# 08_Misc_3.net
KiCad netlist of a schematic drawn in Altium Designer
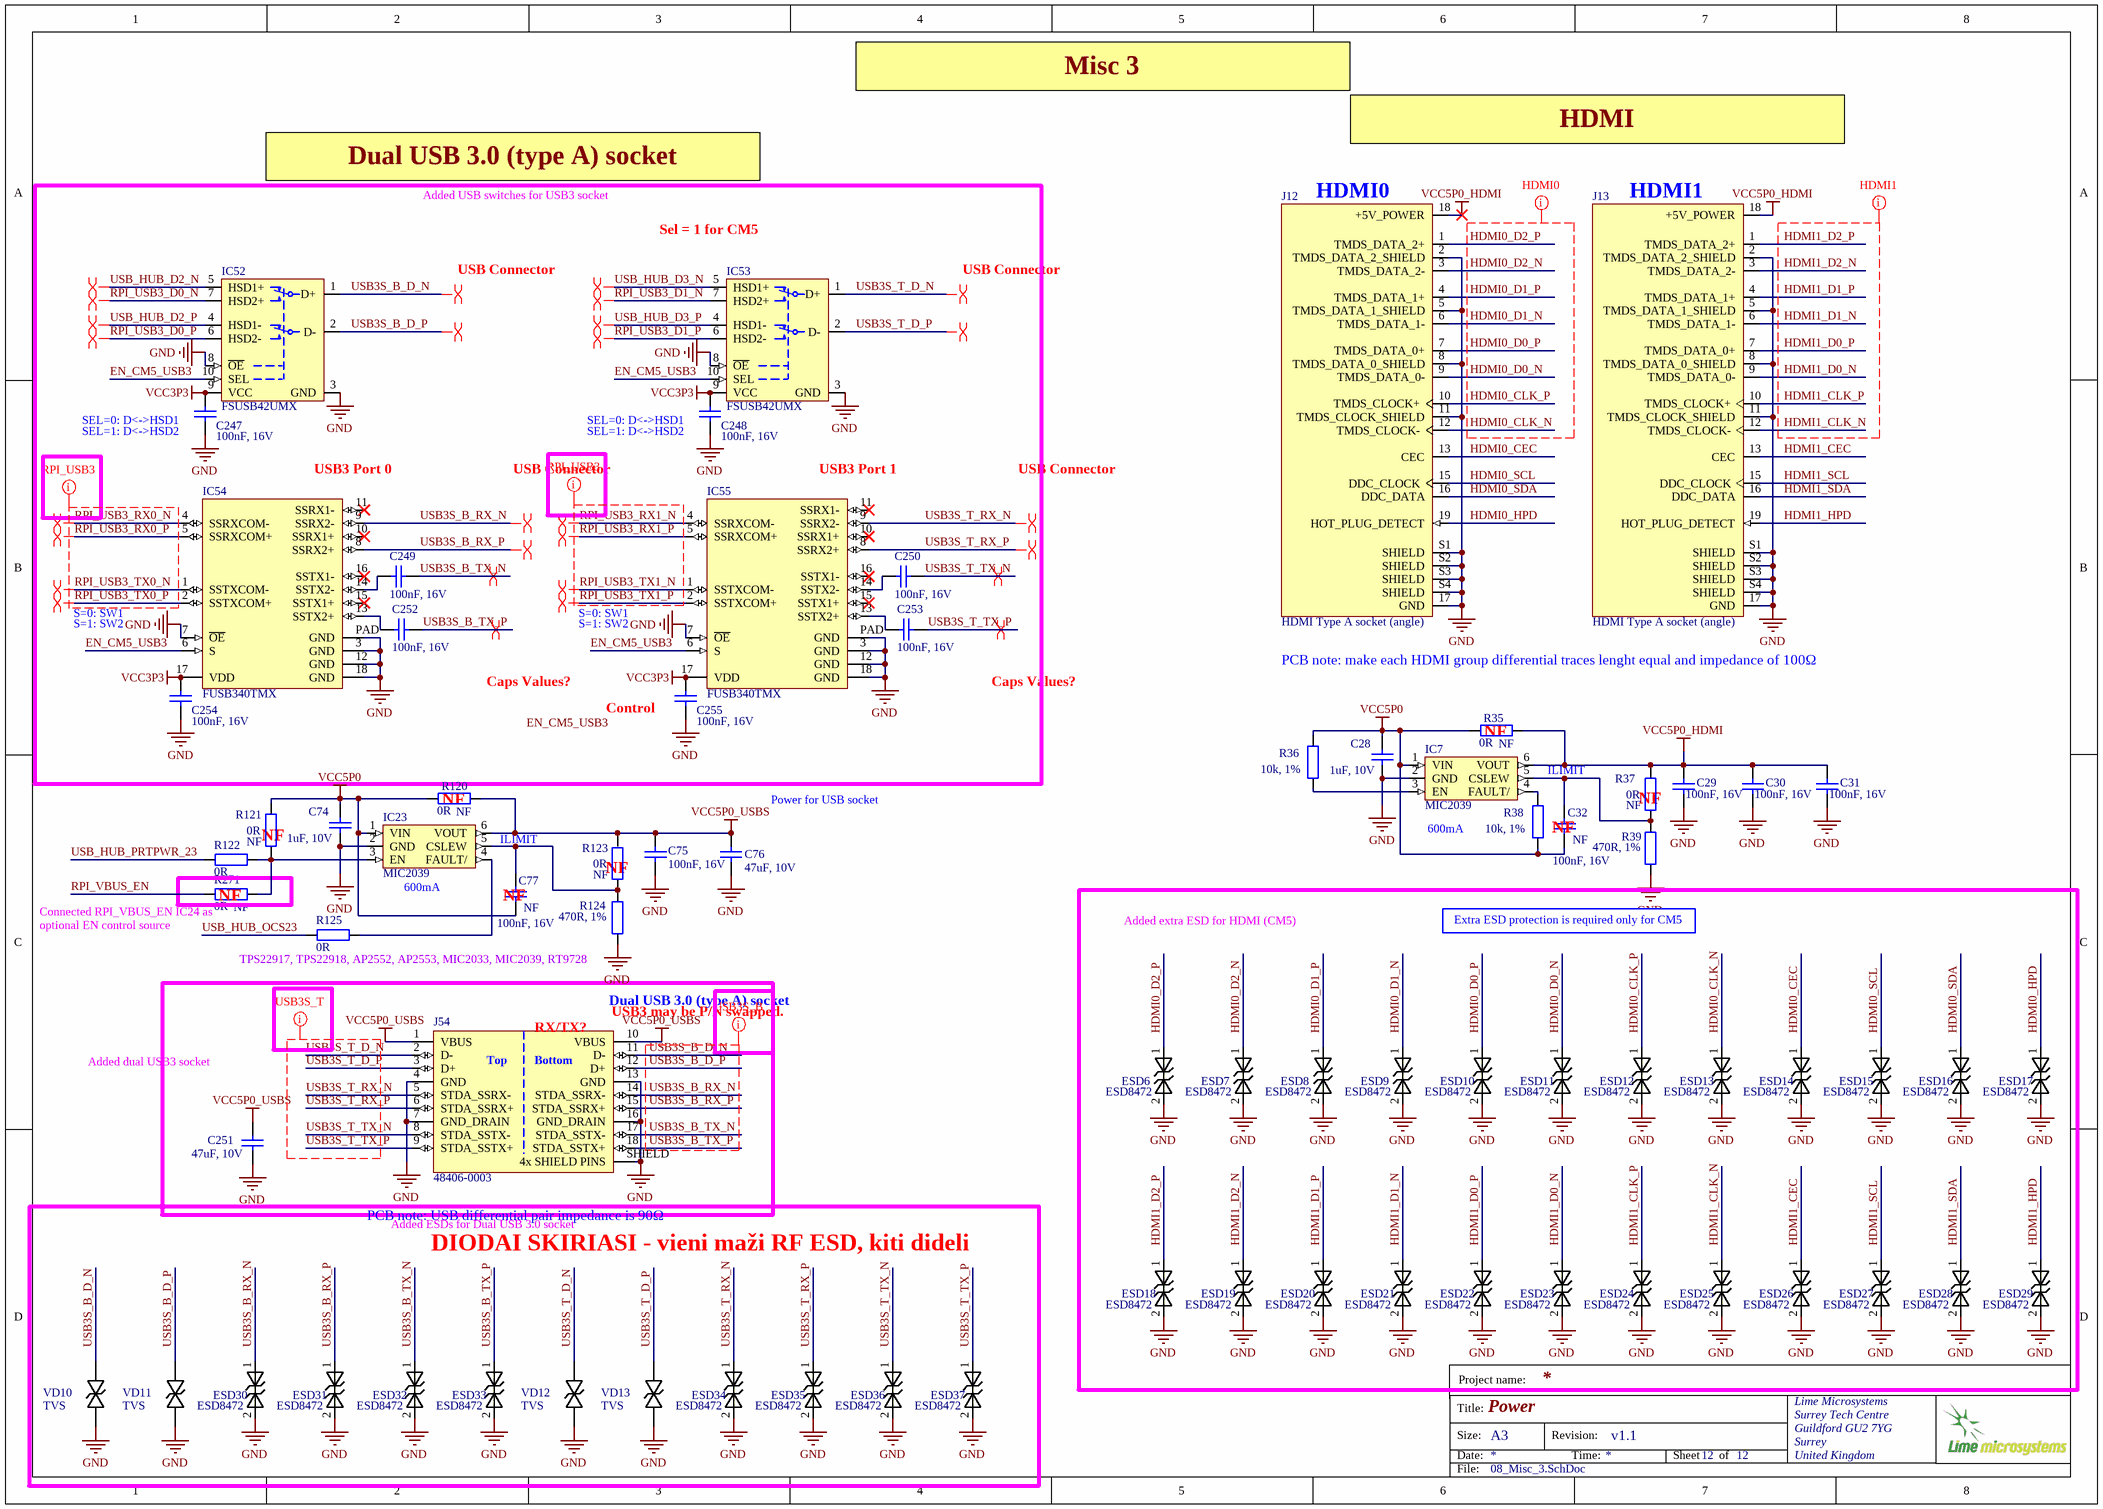
[diagram p0: 08_Misc_3.SchDoc]

(export (version "E")
  (design (tool "Eeschema 10.0.6"))
  (components
    (comp (ref "C28")
      (value "1uF, 10V")
      (footprint "CAP0402")
      (fields (field (name "MANUFACTURER") "Yageo"))
      (libsource (lib "") (part "Cap_0402_1"))
    )
    (comp (ref "C29")
      (value "100nF, 16V")
      (footprint "CAP0402")
      (fields
        (field (name "MANUFACTURER") "Murata Electronics")
        (field (name "TOLERANCE") "10 %")
        (field (name "MANUFACTURER PART NUMBER") "GRM155R71C104KA88D")
      )
      (libsource (lib "") (part "Cap_0402_1"))
    )
    (comp (ref "C30")
      (value "100nF, 16V")
      (footprint "CAP0402")
      (fields
        (field (name "MANUFACTURER") "Murata Electronics")
        (field (name "TOLERANCE") "10 %")
        (field (name "MANUFACTURER PART NUMBER") "GRM155R71C104KA88D")
      )
      (libsource (lib "") (part "Cap_0402_1"))
    )
    (comp (ref "C31")
      (value "100nF, 16V")
      (footprint "CAP0402")
      (fields
        (field (name "MANUFACTURER") "Murata Electronics")
        (field (name "TOLERANCE") "10 %")
        (field (name "MANUFACTURER PART NUMBER") "GRM155R71C104KA88D")
      )
      (libsource (lib "") (part "Cap_0402_1"))
    )
    (comp (ref "C32")
      (value "100nF, 16V")
      (footprint "CAP0402")
      (fields
        (field (name "ASSEMBLY INFO") "NF")
        (field (name "MANUFACTURER") "Murata Electronics")
        (field (name "TOLERANCE") "10 %")
        (field (name "MANUFACTURER PART NUMBER") "GRM155R71C104KA88D")
      )
      (libsource (lib "") (part "Cap_0402_1"))
    )
    (comp (ref "C74")
      (value "1uF, 10V")
      (footprint "CAP0402")
      (fields (field (name "MANUFACTURER") "Yageo"))
      (libsource (lib "") (part "Cap_0402_1"))
    )
    (comp (ref "C75")
      (value "100nF, 16V")
      (footprint "CAP0402")
      (fields
        (field (name "MANUFACTURER") "Murata Electronics")
        (field (name "TOLERANCE") "10 %")
        (field (name "MANUFACTURER PART NUMBER") "GRM155R71C104KA88D")
      )
      (libsource (lib "") (part "Cap_0402_1"))
    )
    (comp (ref "C76")
      (value "47uF, 10V")
      (footprint "CAP1206")
      (fields (field (name "TOLERANCE") "±20%") (field (name "MANUFACTURER") "TDK Corporation"))
      (libsource (lib "LimeFPGAboard_schLib") (part "Cap_1206"))
    )
    (comp (ref "C77")
      (value "100nF, 16V")
      (footprint "CAP0402")
      (fields
        (field (name "ASSEMBLY INFO") "NF")
        (field (name "MANUFACTURER") "Murata Electronics")
        (field (name "TOLERANCE") "10 %")
        (field (name "MANUFACTURER PART NUMBER") "GRM155R71C104KA88D")
      )
      (libsource (lib "") (part "Cap_0402_1"))
    )
    (comp (ref "C247")
      (value "100nF, 16V")
      (footprint "CAP0402")
      (fields
        (field (name "MANUFACTURER") "Murata Electronics")
        (field (name "TOLERANCE") "10 %")
        (field (name "MANUFACTURER PART NUMBER") "GRM155R71C104KA88D")
      )
      (libsource (lib "LimeMicroAltiumLib_schLib") (part "Cap_0402"))
    )
    (comp (ref "C248")
      (value "100nF, 16V")
      (footprint "CAP0402")
      (fields
        (field (name "MANUFACTURER") "Murata Electronics")
        (field (name "TOLERANCE") "10 %")
        (field (name "MANUFACTURER PART NUMBER") "GRM155R71C104KA88D")
      )
      (libsource (lib "LimeMicroAltiumLib_schLib") (part "Cap_0402"))
    )
    (comp (ref "C249")
      (value "100nF, 16V")
      (footprint "CAP0402")
      (fields
        (field (name "MANUFACTURER") "Murata Electronics")
        (field (name "TOLERANCE") "10 %")
        (field (name "MANUFACTURER PART NUMBER") "GRM155R71C104KA88D")
      )
      (libsource (lib "LimeMicroAltiumLib_schLib") (part "Cap_0402"))
    )
    (comp (ref "C250")
      (value "100nF, 16V")
      (footprint "CAP0402")
      (fields
        (field (name "MANUFACTURER") "Murata Electronics")
        (field (name "TOLERANCE") "10 %")
        (field (name "MANUFACTURER PART NUMBER") "GRM155R71C104KA88D")
      )
      (libsource (lib "LimeMicroAltiumLib_schLib") (part "Cap_0402"))
    )
    (comp (ref "C251")
      (value "47uF, 10V")
      (footprint "CAP1206")
      (fields (field (name "TOLERANCE") "±20%") (field (name "MANUFACTURER") "TDK Corporation"))
      (libsource (lib "LimeFPGAboard_schLib") (part "Cap_1206"))
    )
    (comp (ref "C252")
      (value "100nF, 16V")
      (footprint "CAP0402")
      (fields
        (field (name "MANUFACTURER") "Murata Electronics")
        (field (name "TOLERANCE") "10 %")
        (field (name "MANUFACTURER PART NUMBER") "GRM155R71C104KA88D")
      )
      (libsource (lib "LimeMicroAltiumLib_schLib") (part "Cap_0402"))
    )
    (comp (ref "C253")
      (value "100nF, 16V")
      (footprint "CAP0402")
      (fields
        (field (name "MANUFACTURER") "Murata Electronics")
        (field (name "TOLERANCE") "10 %")
        (field (name "MANUFACTURER PART NUMBER") "GRM155R71C104KA88D")
      )
      (libsource (lib "LimeMicroAltiumLib_schLib") (part "Cap_0402"))
    )
    (comp (ref "C254")
      (value "100nF, 16V")
      (footprint "CAP0402")
      (fields
        (field (name "MANUFACTURER") "Murata Electronics")
        (field (name "TOLERANCE") "10 %")
        (field (name "MANUFACTURER PART NUMBER") "GRM155R71C104KA88D")
      )
      (libsource (lib "LimeMicroAltiumLib_schLib") (part "Cap_0402"))
    )
    (comp (ref "C255")
      (value "100nF, 16V")
      (footprint "CAP0402")
      (fields
        (field (name "MANUFACTURER") "Murata Electronics")
        (field (name "TOLERANCE") "10 %")
        (field (name "MANUFACTURER PART NUMBER") "GRM155R71C104KA88D")
      )
      (libsource (lib "LimeMicroAltiumLib_schLib") (part "Cap_0402"))
    )
    (comp (ref "ESD6")
      (value "ESD8472")
      (footprint "ESD8472_X3DFN2")
      (fields (field (name "MANUFACTURER") "ON Semiconductor"))
      (libsource (lib "LimeMicroAltiumLib_schLib") (part "ESD8472"))
    )
    (comp (ref "ESD7")
      (value "ESD8472")
      (footprint "ESD8472_X3DFN2")
      (fields (field (name "MANUFACTURER") "ON Semiconductor"))
      (libsource (lib "LimeMicroAltiumLib_schLib") (part "ESD8472"))
    )
    (comp (ref "ESD8")
      (value "ESD8472")
      (footprint "ESD8472_X3DFN2")
      (fields (field (name "MANUFACTURER") "ON Semiconductor"))
      (libsource (lib "LimeMicroAltiumLib_schLib") (part "ESD8472"))
    )
    (comp (ref "ESD9")
      (value "ESD8472")
      (footprint "ESD8472_X3DFN2")
      (fields (field (name "MANUFACTURER") "ON Semiconductor"))
      (libsource (lib "LimeMicroAltiumLib_schLib") (part "ESD8472"))
    )
    (comp (ref "ESD10")
      (value "ESD8472")
      (footprint "ESD8472_X3DFN2")
      (fields (field (name "MANUFACTURER") "ON Semiconductor"))
      (libsource (lib "LimeMicroAltiumLib_schLib") (part "ESD8472"))
    )
    (comp (ref "ESD11")
      (value "ESD8472")
      (footprint "ESD8472_X3DFN2")
      (fields (field (name "MANUFACTURER") "ON Semiconductor"))
      (libsource (lib "LimeMicroAltiumLib_schLib") (part "ESD8472"))
    )
    (comp (ref "ESD12")
      (value "ESD8472")
      (footprint "ESD8472_X3DFN2")
      (fields (field (name "MANUFACTURER") "ON Semiconductor"))
      (libsource (lib "LimeMicroAltiumLib_schLib") (part "ESD8472"))
    )
    (comp (ref "ESD13")
      (value "ESD8472")
      (footprint "ESD8472_X3DFN2")
      (fields (field (name "MANUFACTURER") "ON Semiconductor"))
      (libsource (lib "LimeMicroAltiumLib_schLib") (part "ESD8472"))
    )
    (comp (ref "ESD14")
      (value "ESD8472")
      (footprint "ESD8472_X3DFN2")
      (fields (field (name "MANUFACTURER") "ON Semiconductor"))
      (libsource (lib "LimeMicroAltiumLib_schLib") (part "ESD8472"))
    )
    (comp (ref "ESD15")
      (value "ESD8472")
      (footprint "ESD8472_X3DFN2")
      (fields (field (name "MANUFACTURER") "ON Semiconductor"))
      (libsource (lib "LimeMicroAltiumLib_schLib") (part "ESD8472"))
    )
    (comp (ref "ESD16")
      (value "ESD8472")
      (footprint "ESD8472_X3DFN2")
      (fields (field (name "MANUFACTURER") "ON Semiconductor"))
      (libsource (lib "LimeMicroAltiumLib_schLib") (part "ESD8472"))
    )
    (comp (ref "ESD17")
      (value "ESD8472")
      (footprint "ESD8472_X3DFN2")
      (fields (field (name "MANUFACTURER") "ON Semiconductor"))
      (libsource (lib "LimeMicroAltiumLib_schLib") (part "ESD8472"))
    )
    (comp (ref "ESD18")
      (value "ESD8472")
      (footprint "ESD8472_X3DFN2")
      (fields (field (name "MANUFACTURER") "ON Semiconductor"))
      (libsource (lib "LimeMicroAltiumLib_schLib") (part "ESD8472"))
    )
    (comp (ref "ESD19")
      (value "ESD8472")
      (footprint "ESD8472_X3DFN2")
      (fields (field (name "MANUFACTURER") "ON Semiconductor"))
      (libsource (lib "LimeMicroAltiumLib_schLib") (part "ESD8472"))
    )
    (comp (ref "ESD20")
      (value "ESD8472")
      (footprint "ESD8472_X3DFN2")
      (fields (field (name "MANUFACTURER") "ON Semiconductor"))
      (libsource (lib "LimeMicroAltiumLib_schLib") (part "ESD8472"))
    )
    (comp (ref "ESD21")
      (value "ESD8472")
      (footprint "ESD8472_X3DFN2")
      (fields (field (name "MANUFACTURER") "ON Semiconductor"))
      (libsource (lib "LimeMicroAltiumLib_schLib") (part "ESD8472"))
    )
    (comp (ref "ESD22")
      (value "ESD8472")
      (footprint "ESD8472_X3DFN2")
      (fields (field (name "MANUFACTURER") "ON Semiconductor"))
      (libsource (lib "LimeMicroAltiumLib_schLib") (part "ESD8472"))
    )
    (comp (ref "ESD23")
      (value "ESD8472")
      (footprint "ESD8472_X3DFN2")
      (fields (field (name "MANUFACTURER") "ON Semiconductor"))
      (libsource (lib "LimeMicroAltiumLib_schLib") (part "ESD8472"))
    )
    (comp (ref "ESD24")
      (value "ESD8472")
      (footprint "ESD8472_X3DFN2")
      (fields (field (name "MANUFACTURER") "ON Semiconductor"))
      (libsource (lib "LimeMicroAltiumLib_schLib") (part "ESD8472"))
    )
    (comp (ref "ESD25")
      (value "ESD8472")
      (footprint "ESD8472_X3DFN2")
      (fields (field (name "MANUFACTURER") "ON Semiconductor"))
      (libsource (lib "LimeMicroAltiumLib_schLib") (part "ESD8472"))
    )
    (comp (ref "ESD26")
      (value "ESD8472")
      (footprint "ESD8472_X3DFN2")
      (fields (field (name "MANUFACTURER") "ON Semiconductor"))
      (libsource (lib "LimeMicroAltiumLib_schLib") (part "ESD8472"))
    )
    (comp (ref "ESD27")
      (value "ESD8472")
      (footprint "ESD8472_X3DFN2")
      (fields (field (name "MANUFACTURER") "ON Semiconductor"))
      (libsource (lib "LimeMicroAltiumLib_schLib") (part "ESD8472"))
    )
    (comp (ref "ESD28")
      (value "ESD8472")
      (footprint "ESD8472_X3DFN2")
      (fields (field (name "MANUFACTURER") "ON Semiconductor"))
      (libsource (lib "LimeMicroAltiumLib_schLib") (part "ESD8472"))
    )
    (comp (ref "ESD29")
      (value "ESD8472")
      (footprint "ESD8472_X3DFN2")
      (fields (field (name "MANUFACTURER") "ON Semiconductor"))
      (libsource (lib "LimeMicroAltiumLib_schLib") (part "ESD8472"))
    )
    (comp (ref "ESD30")
      (value "ESD8472")
      (footprint "ESD8472_X3DFN2")
      (fields (field (name "MANUFACTURER") "ON Semiconductor"))
      (libsource (lib "LimeMicroAltiumLib_schLib") (part "ESD8472"))
    )
    (comp (ref "ESD31")
      (value "ESD8472")
      (footprint "ESD8472_X3DFN2")
      (fields (field (name "MANUFACTURER") "ON Semiconductor"))
      (libsource (lib "LimeMicroAltiumLib_schLib") (part "ESD8472"))
    )
    (comp (ref "ESD32")
      (value "ESD8472")
      (footprint "ESD8472_X3DFN2")
      (fields (field (name "MANUFACTURER") "ON Semiconductor"))
      (libsource (lib "LimeMicroAltiumLib_schLib") (part "ESD8472"))
    )
    (comp (ref "ESD33")
      (value "ESD8472")
      (footprint "ESD8472_X3DFN2")
      (fields (field (name "MANUFACTURER") "ON Semiconductor"))
      (libsource (lib "LimeMicroAltiumLib_schLib") (part "ESD8472"))
    )
    (comp (ref "ESD34")
      (value "ESD8472")
      (footprint "ESD8472_X3DFN2")
      (fields (field (name "MANUFACTURER") "ON Semiconductor"))
      (libsource (lib "LimeMicroAltiumLib_schLib") (part "ESD8472"))
    )
    (comp (ref "ESD35")
      (value "ESD8472")
      (footprint "ESD8472_X3DFN2")
      (fields (field (name "MANUFACTURER") "ON Semiconductor"))
      (libsource (lib "LimeMicroAltiumLib_schLib") (part "ESD8472"))
    )
    (comp (ref "ESD36")
      (value "ESD8472")
      (footprint "ESD8472_X3DFN2")
      (fields (field (name "MANUFACTURER") "ON Semiconductor"))
      (libsource (lib "LimeMicroAltiumLib_schLib") (part "ESD8472"))
    )
    (comp (ref "ESD37")
      (value "ESD8472")
      (footprint "ESD8472_X3DFN2")
      (fields (field (name "MANUFACTURER") "ON Semiconductor"))
      (libsource (lib "LimeMicroAltiumLib_schLib") (part "ESD8472"))
    )
    (comp (ref "IC7")
      (value "MIC2039")
      (footprint "SOT23-6")
      (fields (field (name "MANUFACTURER") "Microchip"))
      (libsource (lib "LimeMicroAltiumLib_schLib_r04") (part "MIC2033_power_switch"))
    )
    (comp (ref "IC23")
      (value "MIC2039")
      (footprint "SOT23-6")
      (fields (field (name "MANUFACTURER") "Microchip"))
      (libsource (lib "LimeMicroAltiumLib_schLib_r04") (part "MIC2033_power_switch"))
    )
    (comp (ref "IC52")
      (value "FSUSB42UMX")
      (footprint "FSUSB42UMX")
      (fields (field (name "MANUFACTURER") "ON Semiconductor") (field (name "BASE PART NUMBER") "FSUSB42"))
      (libsource (lib "LimeMicroAltiumLib_schLib_r01") (part "FSUSB42UMX"))
    )
    (comp (ref "IC53")
      (value "FSUSB42UMX")
      (footprint "FSUSB42UMX")
      (fields (field (name "MANUFACTURER") "ON Semiconductor") (field (name "BASE PART NUMBER") "FSUSB42"))
      (libsource (lib "LimeMicroAltiumLib_schLib_r01") (part "FSUSB42UMX"))
    )
    (comp (ref "IC54")
      (value "FUSB340TMX")
      (footprint "FUSB340TMX_USB_switch_18-XFQFN")
      (fields (field (name "MANUFACTURER") "ON Semiconductor / Fairchild"))
      (libsource (lib "LimeMicroAltiumLib") (part "FUSB340TMX_USB_switch"))
    )
    (comp (ref "IC55")
      (value "FUSB340TMX")
      (footprint "FUSB340TMX_USB_switch_18-XFQFN")
      (fields (field (name "MANUFACTURER") "ON Semiconductor / Fairchild"))
      (libsource (lib "LimeMicroAltiumLib") (part "FUSB340TMX_USB_switch"))
    )
    (comp (ref "J12")
      (value "HDMI Type A socket (angle)")
      (footprint "HDMI_HD01-19-RA-TH")
      (fields (field (name "MANUFACTURER") "CUI Devices"))
      (libsource (lib "LimeMicroAltiumLib_schLib_r04") (part "HDMI_HD01-19-RA-TH"))
    )
    (comp (ref "J13")
      (value "HDMI Type A socket (angle)")
      (footprint "HDMI_HD01-19-RA-TH")
      (fields (field (name "MANUFACTURER") "CUI Devices"))
      (libsource (lib "LimeMicroAltiumLib_schLib_r04") (part "HDMI_HD01-19-RA-TH"))
    )
    (comp (ref "J54")
      (value "48406-0003")
      (footprint "Dual_USB_48406-0003_Molex")
      (fields (field (name "MANUFACTURER") "Molex"))
      (libsource (lib "LimeMicroAltiumLib") (part "Dual_USB_48406-0003_Molex"))
    )
    (comp (ref "R35")
      (value "0R")
      (footprint "RES0402")
      (fields
        (field (name "ASSEMBLY INFO") "NF")
        (field (name "MANUFACTURER") "Yageo")
        (field (name "TOLERANCE") "Jumper")
      )
      (libsource (lib "") (part "Res_0402_1"))
    )
    (comp (ref "R36")
      (value "10k, 1%")
      (footprint "RES0402")
      (fields (field (name "MANUFACTURER") "Yageo") (field (name "TOLERANCE") "±1%"))
      (libsource (lib "LimeMicroAltiumLib_schLib") (part "Res_0402"))
    )
    (comp (ref "R37")
      (value "0R")
      (footprint "RES0402")
      (fields
        (field (name "ASSEMBLY INFO") "NF")
        (field (name "MANUFACTURER") "Yageo")
        (field (name "TOLERANCE") "Jumper")
      )
      (libsource (lib "") (part "Res_0402_1"))
    )
    (comp (ref "R38")
      (value "10k, 1%")
      (footprint "RES0402")
      (fields (field (name "MANUFACTURER") "Yageo") (field (name "TOLERANCE") "±1%"))
      (libsource (lib "LimeMicroAltiumLib_schLib") (part "Res_0402"))
    )
    (comp (ref "R39")
      (value "470R, 1%")
      (footprint "RES0402")
      (fields (field (name "TOLERANCE") "1%") (field (name "MANUFACTURER") "Yageo"))
      (libsource (lib "") (part "Res_0402_1"))
    )
    (comp (ref "R120")
      (value "0R")
      (footprint "RES0402")
      (fields
        (field (name "ASSEMBLY INFO") "NF")
        (field (name "MANUFACTURER") "Yageo")
        (field (name "TOLERANCE") "Jumper")
      )
      (libsource (lib "") (part "Res_0402_1"))
    )
    (comp (ref "R121")
      (value "0R")
      (footprint "RES0402")
      (fields
        (field (name "ASSEMBLY INFO") "NF")
        (field (name "MANUFACTURER") "Yageo")
        (field (name "TOLERANCE") "Jumper")
      )
      (libsource (lib "") (part "Res_0402_1"))
    )
    (comp (ref "R122")
      (value "0R")
      (footprint "RES0402")
      (fields (field (name "MANUFACTURER") "Yageo") (field (name "TOLERANCE") "Jumper"))
      (libsource (lib "") (part "Res_0402_1"))
    )
    (comp (ref "R123")
      (value "0R")
      (footprint "RES0402")
      (fields
        (field (name "ASSEMBLY INFO") "NF")
        (field (name "MANUFACTURER") "Yageo")
        (field (name "TOLERANCE") "Jumper")
      )
      (libsource (lib "") (part "Res_0402_1"))
    )
    (comp (ref "R124")
      (value "470R, 1%")
      (footprint "RES0402")
      (fields (field (name "TOLERANCE") "1%") (field (name "MANUFACTURER") "Yageo"))
      (libsource (lib "") (part "Res_0402_1"))
    )
    (comp (ref "R125")
      (value "0R")
      (footprint "RES0402")
      (fields (field (name "MANUFACTURER") "Yageo") (field (name "TOLERANCE") "Jumper"))
      (libsource (lib "") (part "Res_0402_1"))
    )
    (comp (ref "R271")
      (value "0R")
      (footprint "RES0402")
      (fields
        (field (name "ASSEMBLY INFO") "NF")
        (field (name "MANUFACTURER") "Yageo")
        (field (name "TOLERANCE") "Jumper")
      )
      (libsource (lib "") (part "Res_0402_1"))
    )
    (comp (ref "VD10")
      (value "TVS")
      (footprint "SOD323")
      (fields
        (field (name "MANUFACTURER PART NUMBER") "SD03LCC")
        (field (name "MANUFACTURER") "Sangdest Microelectronics")
      )
      (libsource (lib "LimeNet-Micro_2v1-SDR") (part "DIODE_TVS"))
    )
    (comp (ref "VD11")
      (value "TVS")
      (footprint "SOD323")
      (fields
        (field (name "MANUFACTURER PART NUMBER") "SD03LCC")
        (field (name "MANUFACTURER") "Sangdest Microelectronics")
      )
      (libsource (lib "LimeNet-Micro_2v1-SDR") (part "DIODE_TVS"))
    )
    (comp (ref "VD12")
      (value "TVS")
      (footprint "SOD323")
      (fields
        (field (name "MANUFACTURER PART NUMBER") "SD03LCC")
        (field (name "MANUFACTURER") "Sangdest Microelectronics")
      )
      (libsource (lib "LimeNet-Micro_2v1-SDR") (part "DIODE_TVS"))
    )
    (comp (ref "VD13")
      (value "TVS")
      (footprint "SOD323")
      (fields
        (field (name "MANUFACTURER PART NUMBER") "SD03LCC")
        (field (name "MANUFACTURER") "Sangdest Microelectronics")
      )
      (libsource (lib "LimeNet-Micro_2v1-SDR") (part "DIODE_TVS"))
    )
  )
  (nets
    (net (code "1") (name "/EN_CM5_USB3") (class "Default")
      (node (ref "IC52") (pin "10") (pinfunction "SEL_10") (pintype "input"))
      (node (ref "IC53") (pin "10") (pinfunction "SEL_10") (pintype "input"))
      (node (ref "IC54") (pin "6") (pinfunction "S_6") (pintype "input"))
      (node (ref "IC55") (pin "6") (pinfunction "S_6") (pintype "input"))
    )
    (net (code "2") (name "/HDMI0_CEC") (class "Default")
      (node (ref "ESD14") (pin "1") (pinfunction "1_1") (pintype "passive"))
      (node (ref "J12") (pin "13") (pinfunction "CEC_13") (pintype "bidirectional"))
    )
    (net (code "3") (name "/HDMI0_CLK_N") (class "Default")
      (node (ref "ESD13") (pin "1") (pinfunction "1_1") (pintype "passive"))
      (node (ref "J12") (pin "12") (pinfunction "TMDS_CLOCK-_12") (pintype "bidirectional"))
    )
    (net (code "4") (name "/HDMI0_CLK_P") (class "Default")
      (node (ref "ESD12") (pin "1") (pinfunction "1_1") (pintype "passive"))
      (node (ref "J12") (pin "10") (pinfunction "TMDS_CLOCK+_10") (pintype "bidirectional"))
    )
    (net (code "5") (name "/HDMI0_D0_N") (class "Default")
      (node (ref "ESD11") (pin "1") (pinfunction "1_1") (pintype "passive"))
      (node (ref "J12") (pin "9") (pinfunction "TMDS_DATA_0-_9") (pintype "bidirectional"))
    )
    (net (code "6") (name "/HDMI0_D0_P") (class "Default")
      (node (ref "ESD10") (pin "1") (pinfunction "1_1") (pintype "passive"))
      (node (ref "J12") (pin "7") (pinfunction "TMDS_DATA_0+_7") (pintype "bidirectional"))
    )
    (net (code "7") (name "/HDMI0_D1_N") (class "Default")
      (node (ref "ESD9") (pin "1") (pinfunction "1_1") (pintype "passive"))
      (node (ref "J12") (pin "6") (pinfunction "TMDS_DATA_1-_6") (pintype "bidirectional"))
    )
    (net (code "8") (name "/HDMI0_D1_P") (class "Default")
      (node (ref "ESD8") (pin "1") (pinfunction "1_1") (pintype "passive"))
      (node (ref "J12") (pin "4") (pinfunction "TMDS_DATA_1+_4") (pintype "bidirectional"))
    )
    (net (code "9") (name "/HDMI0_D2_N") (class "Default")
      (node (ref "ESD7") (pin "1") (pinfunction "1_1") (pintype "passive"))
      (node (ref "J12") (pin "3") (pinfunction "TMDS_DATA_2-_3") (pintype "bidirectional"))
    )
    (net (code "10") (name "/HDMI0_D2_P") (class "Default")
      (node (ref "ESD6") (pin "1") (pinfunction "1_1") (pintype "passive"))
      (node (ref "J12") (pin "1") (pinfunction "TMDS_DATA_2+_1") (pintype "bidirectional"))
    )
    (net (code "11") (name "/HDMI0_HPD") (class "Default")
      (node (ref "ESD17") (pin "1") (pinfunction "1_1") (pintype "passive"))
      (node (ref "J12") (pin "19") (pinfunction "HOT_PLUG_DETECT_19") (pintype "input"))
    )
    (net (code "12") (name "/HDMI0_SCL") (class "Default")
      (node (ref "ESD15") (pin "1") (pinfunction "1_1") (pintype "passive"))
      (node (ref "J12") (pin "15") (pinfunction "DDC_CLOCK_15") (pintype "bidirectional"))
    )
    (net (code "13") (name "/HDMI0_SDA") (class "Default")
      (node (ref "ESD16") (pin "1") (pinfunction "1_1") (pintype "passive"))
      (node (ref "J12") (pin "16") (pinfunction "DDC_DATA_16") (pintype "bidirectional"))
    )
    (net (code "14") (name "/HDMI1_CEC") (class "Default")
      (node (ref "ESD26") (pin "1") (pinfunction "1_1") (pintype "passive"))
      (node (ref "J13") (pin "13") (pinfunction "CEC_13") (pintype "bidirectional"))
    )
    (net (code "15") (name "/HDMI1_CLK_N") (class "Default")
      (node (ref "ESD25") (pin "1") (pinfunction "1_1") (pintype "passive"))
      (node (ref "J13") (pin "12") (pinfunction "TMDS_CLOCK-_12") (pintype "bidirectional"))
    )
    (net (code "16") (name "/HDMI1_CLK_P") (class "Default")
      (node (ref "ESD24") (pin "1") (pinfunction "1_1") (pintype "passive"))
      (node (ref "J13") (pin "10") (pinfunction "TMDS_CLOCK+_10") (pintype "bidirectional"))
    )
    (net (code "17") (name "/HDMI1_D0_N") (class "Default")
      (node (ref "ESD23") (pin "1") (pinfunction "1_1") (pintype "passive"))
      (node (ref "J13") (pin "9") (pinfunction "TMDS_DATA_0-_9") (pintype "bidirectional"))
    )
    (net (code "18") (name "/HDMI1_D0_P") (class "Default")
      (node (ref "ESD22") (pin "1") (pinfunction "1_1") (pintype "passive"))
      (node (ref "J13") (pin "7") (pinfunction "TMDS_DATA_0+_7") (pintype "bidirectional"))
    )
    (net (code "19") (name "/HDMI1_D1_N") (class "Default")
      (node (ref "ESD21") (pin "1") (pinfunction "1_1") (pintype "passive"))
      (node (ref "J13") (pin "6") (pinfunction "TMDS_DATA_1-_6") (pintype "bidirectional"))
    )
    (net (code "20") (name "/HDMI1_D1_P") (class "Default")
      (node (ref "ESD20") (pin "1") (pinfunction "1_1") (pintype "passive"))
      (node (ref "J13") (pin "4") (pinfunction "TMDS_DATA_1+_4") (pintype "bidirectional"))
    )
    (net (code "21") (name "/HDMI1_D2_N") (class "Default")
      (node (ref "ESD19") (pin "1") (pinfunction "1_1") (pintype "passive"))
      (node (ref "J13") (pin "3") (pinfunction "TMDS_DATA_2-_3") (pintype "bidirectional"))
    )
    (net (code "22") (name "/HDMI1_D2_P") (class "Default")
      (node (ref "ESD18") (pin "1") (pinfunction "1_1") (pintype "passive"))
      (node (ref "J13") (pin "1") (pinfunction "TMDS_DATA_2+_1") (pintype "bidirectional"))
    )
    (net (code "23") (name "/HDMI1_HPD") (class "Default")
      (node (ref "ESD29") (pin "1") (pinfunction "1_1") (pintype "passive"))
      (node (ref "J13") (pin "19") (pinfunction "HOT_PLUG_DETECT_19") (pintype "input"))
    )
    (net (code "24") (name "/HDMI1_SCL") (class "Default")
      (node (ref "ESD27") (pin "1") (pinfunction "1_1") (pintype "passive"))
      (node (ref "J13") (pin "15") (pinfunction "DDC_CLOCK_15") (pintype "bidirectional"))
    )
    (net (code "25") (name "/HDMI1_SDA") (class "Default")
      (node (ref "ESD28") (pin "1") (pinfunction "1_1") (pintype "passive"))
      (node (ref "J13") (pin "16") (pinfunction "DDC_DATA_16") (pintype "bidirectional"))
    )
    (net (code "26") (name "/RPI_USB3_D0_N") (class "Default")
      (node (ref "IC52") (pin "7") (pinfunction "HSD2+_7") (pintype "passive"))
    )
    (net (code "27") (name "/RPI_USB3_D0_P") (class "Default")
      (node (ref "IC52") (pin "6") (pinfunction "HSD2-_6") (pintype "passive"))
    )
    (net (code "28") (name "/RPI_USB3_D1_N") (class "Default")
      (node (ref "IC53") (pin "7") (pinfunction "HSD2+_7") (pintype "passive"))
    )
    (net (code "29") (name "/RPI_USB3_D1_P") (class "Default")
      (node (ref "IC53") (pin "6") (pinfunction "HSD2-_6") (pintype "passive"))
    )
    (net (code "30") (name "/RPI_USB3_RX0_N") (class "Default")
      (node (ref "IC54") (pin "4") (pinfunction "SSRXCOM-_4") (pintype "bidirectional"))
    )
    (net (code "31") (name "/RPI_USB3_RX0_P") (class "Default")
      (node (ref "IC54") (pin "5") (pinfunction "SSRXCOM+_5") (pintype "bidirectional"))
    )
    (net (code "32") (name "/RPI_USB3_RX1_N") (class "Default")
      (node (ref "IC55") (pin "4") (pinfunction "SSRXCOM-_4") (pintype "bidirectional"))
    )
    (net (code "33") (name "/RPI_USB3_RX1_P") (class "Default")
      (node (ref "IC55") (pin "5") (pinfunction "SSRXCOM+_5") (pintype "bidirectional"))
    )
    (net (code "34") (name "/RPI_USB3_TX0_N") (class "Default")
      (node (ref "IC54") (pin "1") (pinfunction "SSTXCOM-_1") (pintype "bidirectional"))
    )
    (net (code "35") (name "/RPI_USB3_TX0_P") (class "Default")
      (node (ref "IC54") (pin "2") (pinfunction "SSTXCOM+_2") (pintype "bidirectional"))
    )
    (net (code "36") (name "/RPI_USB3_TX1_N") (class "Default")
      (node (ref "IC55") (pin "1") (pinfunction "SSTXCOM-_1") (pintype "bidirectional"))
    )
    (net (code "37") (name "/RPI_USB3_TX1_P") (class "Default")
      (node (ref "IC55") (pin "2") (pinfunction "SSTXCOM+_2") (pintype "bidirectional"))
    )
    (net (code "38") (name "/RPI_VBUS_EN") (class "Default")
      (node (ref "R271") (pin "2") (pinfunction "2_2") (pintype "passive"))
    )
    (net (code "39") (name "/USB3S_B_D_N") (class "Default")
      (node (ref "IC52") (pin "1") (pinfunction "D+_1") (pintype "passive"))
      (node (ref "J54") (pin "11") (pinfunction "D-_11") (pintype "bidirectional"))
      (node (ref "VD10") (pin "A") (pinfunction "A_A") (pintype "passive"))
    )
    (net (code "40") (name "/USB3S_B_D_P") (class "Default")
      (node (ref "IC52") (pin "2") (pinfunction "D-_2") (pintype "passive"))
      (node (ref "J54") (pin "12") (pinfunction "D+_12") (pintype "bidirectional"))
      (node (ref "VD11") (pin "A") (pinfunction "A_A") (pintype "passive"))
    )
    (net (code "41") (name "/USB3S_B_RX_N") (class "Default")
      (node (ref "ESD30") (pin "1") (pinfunction "1_1") (pintype "passive"))
      (node (ref "IC54") (pin "9") (pinfunction "SSRX2-_9") (pintype "bidirectional"))
      (node (ref "J54") (pin "14") (pinfunction "STDA_SSRX-_14") (pintype "bidirectional"))
    )
    (net (code "42") (name "/USB3S_B_RX_P") (class "Default")
      (node (ref "ESD31") (pin "1") (pinfunction "1_1") (pintype "passive"))
      (node (ref "IC54") (pin "8") (pinfunction "SSRX2+_8") (pintype "bidirectional"))
      (node (ref "J54") (pin "15") (pinfunction "STDA_SSRX+_15") (pintype "bidirectional"))
    )
    (net (code "43") (name "/USB3S_B_TX_N") (class "Default")
      (node (ref "C249") (pin "2") (pinfunction "2_2") (pintype "passive"))
      (node (ref "ESD32") (pin "1") (pinfunction "1_1") (pintype "passive"))
      (node (ref "J54") (pin "17") (pinfunction "STDA_SSTX-_17") (pintype "bidirectional"))
    )
    (net (code "44") (name "/USB3S_B_TX_P") (class "Default")
      (node (ref "C252") (pin "2") (pinfunction "2_2") (pintype "passive"))
      (node (ref "ESD33") (pin "1") (pinfunction "1_1") (pintype "passive"))
      (node (ref "J54") (pin "18") (pinfunction "STDA_SSTX+_18") (pintype "bidirectional"))
    )
    (net (code "45") (name "/USB3S_T_D_N") (class "Default")
      (node (ref "IC53") (pin "1") (pinfunction "D+_1") (pintype "passive"))
      (node (ref "J54") (pin "2") (pinfunction "D-_2") (pintype "bidirectional"))
      (node (ref "VD12") (pin "A") (pinfunction "A_A") (pintype "passive"))
    )
    (net (code "46") (name "/USB3S_T_D_P") (class "Default")
      (node (ref "IC53") (pin "2") (pinfunction "D-_2") (pintype "passive"))
      (node (ref "J54") (pin "3") (pinfunction "D+_3") (pintype "bidirectional"))
      (node (ref "VD13") (pin "A") (pinfunction "A_A") (pintype "passive"))
    )
    (net (code "47") (name "/USB3S_T_RX_N") (class "Default")
      (node (ref "ESD34") (pin "1") (pinfunction "1_1") (pintype "passive"))
      (node (ref "IC55") (pin "9") (pinfunction "SSRX2-_9") (pintype "bidirectional"))
      (node (ref "J54") (pin "5") (pinfunction "STDA_SSRX-_5") (pintype "bidirectional"))
    )
    (net (code "48") (name "/USB3S_T_RX_P") (class "Default")
      (node (ref "ESD35") (pin "1") (pinfunction "1_1") (pintype "passive"))
      (node (ref "IC55") (pin "8") (pinfunction "SSRX2+_8") (pintype "bidirectional"))
      (node (ref "J54") (pin "6") (pinfunction "STDA_SSRX+_6") (pintype "bidirectional"))
    )
    (net (code "49") (name "/USB3S_T_TX_N") (class "Default")
      (node (ref "C250") (pin "2") (pinfunction "2_2") (pintype "passive"))
      (node (ref "ESD36") (pin "1") (pinfunction "1_1") (pintype "passive"))
      (node (ref "J54") (pin "8") (pinfunction "STDA_SSTX-_8") (pintype "bidirectional"))
    )
    (net (code "50") (name "/USB3S_T_TX_P") (class "Default")
      (node (ref "C253") (pin "2") (pinfunction "2_2") (pintype "passive"))
      (node (ref "ESD37") (pin "1") (pinfunction "1_1") (pintype "passive"))
      (node (ref "J54") (pin "9") (pinfunction "STDA_SSTX+_9") (pintype "bidirectional"))
    )
    (net (code "51") (name "/USB_HUB_D2_N") (class "Default")
      (node (ref "IC52") (pin "5") (pinfunction "HSD1+_5") (pintype "passive"))
    )
    (net (code "52") (name "/USB_HUB_D2_P") (class "Default")
      (node (ref "IC52") (pin "4") (pinfunction "HSD1-_4") (pintype "passive"))
    )
    (net (code "53") (name "/USB_HUB_D3_N") (class "Default")
      (node (ref "IC53") (pin "5") (pinfunction "HSD1+_5") (pintype "passive"))
    )
    (net (code "54") (name "/USB_HUB_D3_P") (class "Default")
      (node (ref "IC53") (pin "4") (pinfunction "HSD1-_4") (pintype "passive"))
    )
    (net (code "55") (name "/USB_HUB_OCS23") (class "Default")
      (node (ref "R125") (pin "2") (pinfunction "2_2") (pintype "passive"))
    )
    (net (code "56") (name "/USB_HUB_PRTPWR_23") (class "Default")
      (node (ref "R122") (pin "2") (pinfunction "2_2") (pintype "passive"))
    )
    (net (code "57") (name "GND") (class "Default")
      (node (ref "C247") (pin "2") (pinfunction "2_2") (pintype "passive"))
      (node (ref "C248") (pin "2") (pinfunction "2_2") (pintype "passive"))
      (node (ref "C251") (pin "1") (pinfunction "1_1") (pintype "passive"))
      (node (ref "C254") (pin "2") (pinfunction "2_2") (pintype "passive"))
      (node (ref "C255") (pin "2") (pinfunction "2_2") (pintype "passive"))
      (node (ref "C28") (pin "2") (pinfunction "2_2") (pintype "passive"))
      (node (ref "C29") (pin "2") (pinfunction "2_2") (pintype "passive"))
      (node (ref "C30") (pin "2") (pinfunction "2_2") (pintype "passive"))
      (node (ref "C31") (pin "2") (pinfunction "2_2") (pintype "passive"))
      (node (ref "C74") (pin "2") (pinfunction "2_2") (pintype "passive"))
      (node (ref "C75") (pin "2") (pinfunction "2_2") (pintype "passive"))
      (node (ref "C76") (pin "1") (pinfunction "1_1") (pintype "passive"))
      (node (ref "ESD10") (pin "2") (pinfunction "2_2") (pintype "passive"))
      (node (ref "ESD11") (pin "2") (pinfunction "2_2") (pintype "passive"))
      (node (ref "ESD12") (pin "2") (pinfunction "2_2") (pintype "passive"))
      (node (ref "ESD13") (pin "2") (pinfunction "2_2") (pintype "passive"))
      (node (ref "ESD14") (pin "2") (pinfunction "2_2") (pintype "passive"))
      (node (ref "ESD15") (pin "2") (pinfunction "2_2") (pintype "passive"))
      (node (ref "ESD16") (pin "2") (pinfunction "2_2") (pintype "passive"))
      (node (ref "ESD17") (pin "2") (pinfunction "2_2") (pintype "passive"))
      (node (ref "ESD18") (pin "2") (pinfunction "2_2") (pintype "passive"))
      (node (ref "ESD19") (pin "2") (pinfunction "2_2") (pintype "passive"))
      (node (ref "ESD20") (pin "2") (pinfunction "2_2") (pintype "passive"))
      (node (ref "ESD21") (pin "2") (pinfunction "2_2") (pintype "passive"))
      (node (ref "ESD22") (pin "2") (pinfunction "2_2") (pintype "passive"))
      (node (ref "ESD23") (pin "2") (pinfunction "2_2") (pintype "passive"))
      (node (ref "ESD24") (pin "2") (pinfunction "2_2") (pintype "passive"))
      (node (ref "ESD25") (pin "2") (pinfunction "2_2") (pintype "passive"))
      (node (ref "ESD26") (pin "2") (pinfunction "2_2") (pintype "passive"))
      (node (ref "ESD27") (pin "2") (pinfunction "2_2") (pintype "passive"))
      (node (ref "ESD28") (pin "2") (pinfunction "2_2") (pintype "passive"))
      (node (ref "ESD29") (pin "2") (pinfunction "2_2") (pintype "passive"))
      (node (ref "ESD30") (pin "2") (pinfunction "2_2") (pintype "passive"))
      (node (ref "ESD31") (pin "2") (pinfunction "2_2") (pintype "passive"))
      (node (ref "ESD32") (pin "2") (pinfunction "2_2") (pintype "passive"))
      (node (ref "ESD33") (pin "2") (pinfunction "2_2") (pintype "passive"))
      (node (ref "ESD34") (pin "2") (pinfunction "2_2") (pintype "passive"))
      (node (ref "ESD35") (pin "2") (pinfunction "2_2") (pintype "passive"))
      (node (ref "ESD36") (pin "2") (pinfunction "2_2") (pintype "passive"))
      (node (ref "ESD37") (pin "2") (pinfunction "2_2") (pintype "passive"))
      (node (ref "ESD6") (pin "2") (pinfunction "2_2") (pintype "passive"))
      (node (ref "ESD7") (pin "2") (pinfunction "2_2") (pintype "passive"))
      (node (ref "ESD8") (pin "2") (pinfunction "2_2") (pintype "passive"))
      (node (ref "ESD9") (pin "2") (pinfunction "2_2") (pintype "passive"))
      (node (ref "IC23") (pin "2") (pinfunction "GND_2") (pintype "passive"))
      (node (ref "IC52") (pin "3") (pinfunction "GND_3") (pintype "passive"))
      (node (ref "IC52") (pin "8") (pinfunction "~{OE}_8") (pintype "input"))
      (node (ref "IC53") (pin "3") (pinfunction "GND_3") (pintype "passive"))
      (node (ref "IC53") (pin "8") (pinfunction "~{OE}_8") (pintype "input"))
      (node (ref "IC54") (pin "12") (pinfunction "GND_12") (pintype "passive"))
      (node (ref "IC54") (pin "18") (pinfunction "GND_18") (pintype "passive"))
      (node (ref "IC54") (pin "3") (pinfunction "GND_3") (pintype "passive"))
      (node (ref "IC54") (pin "7") (pinfunction "~{OE}_7") (pintype "input"))
      (node (ref "IC54") (pin "PAD") (pinfunction "GND_PAD") (pintype "passive"))
      (node (ref "IC55") (pin "12") (pinfunction "GND_12") (pintype "passive"))
      (node (ref "IC55") (pin "18") (pinfunction "GND_18") (pintype "passive"))
      (node (ref "IC55") (pin "3") (pinfunction "GND_3") (pintype "passive"))
      (node (ref "IC55") (pin "7") (pinfunction "~{OE}_7") (pintype "input"))
      (node (ref "IC55") (pin "PAD") (pinfunction "GND_PAD") (pintype "passive"))
      (node (ref "IC7") (pin "2") (pinfunction "GND_2") (pintype "passive"))
      (node (ref "J12") (pin "11") (pinfunction "TMDS_CLOCK_SHIELD_11") (pintype "passive"))
      (node (ref "J12") (pin "17") (pinfunction "GND_17") (pintype "power_in"))
      (node (ref "J12") (pin "2") (pinfunction "TMDS_DATA_2_SHIELD_2") (pintype "passive"))
      (node (ref "J12") (pin "5") (pinfunction "TMDS_DATA_1_SHIELD_5") (pintype "passive"))
      (node (ref "J12") (pin "8") (pinfunction "TMDS_DATA_0_SHIELD_8") (pintype "passive"))
      (node (ref "J12") (pin "S1") (pinfunction "SHIELD_S1") (pintype "passive"))
      (node (ref "J12") (pin "S2") (pinfunction "SHIELD_S2") (pintype "passive"))
      (node (ref "J12") (pin "S3") (pinfunction "SHIELD_S3") (pintype "passive"))
      (node (ref "J12") (pin "S4") (pinfunction "SHIELD_S4") (pintype "passive"))
      (node (ref "J13") (pin "11") (pinfunction "TMDS_CLOCK_SHIELD_11") (pintype "passive"))
      (node (ref "J13") (pin "17") (pinfunction "GND_17") (pintype "power_in"))
      (node (ref "J13") (pin "2") (pinfunction "TMDS_DATA_2_SHIELD_2") (pintype "passive"))
      (node (ref "J13") (pin "5") (pinfunction "TMDS_DATA_1_SHIELD_5") (pintype "passive"))
      (node (ref "J13") (pin "8") (pinfunction "TMDS_DATA_0_SHIELD_8") (pintype "passive"))
      (node (ref "J13") (pin "S1") (pinfunction "SHIELD_S1") (pintype "passive"))
      (node (ref "J13") (pin "S2") (pinfunction "SHIELD_S2") (pintype "passive"))
      (node (ref "J13") (pin "S3") (pinfunction "SHIELD_S3") (pintype "passive"))
      (node (ref "J13") (pin "S4") (pinfunction "SHIELD_S4") (pintype "passive"))
      (node (ref "J54") (pin "13") (pinfunction "GND_13") (pintype "passive"))
      (node (ref "J54") (pin "16") (pinfunction "GND_DRAIN_16") (pintype "passive"))
      (node (ref "J54") (pin "4") (pinfunction "GND_4") (pintype "passive"))
      (node (ref "J54") (pin "7") (pinfunction "GND_DRAIN_7") (pintype "passive"))
      (node (ref "J54") (pin "SHIELD") (pinfunction "4x_SHIELD_PINS_SHIELD") (pintype "passive"))
      (node (ref "R124") (pin "1") (pinfunction "1_1") (pintype "passive"))
      (node (ref "R39") (pin "1") (pinfunction "1_1") (pintype "passive"))
      (node (ref "VD10") (pin "K") (pinfunction "K_K") (pintype "passive"))
      (node (ref "VD11") (pin "K") (pinfunction "K_K") (pintype "passive"))
      (node (ref "VD12") (pin "K") (pinfunction "K_K") (pintype "passive"))
      (node (ref "VD13") (pin "K") (pinfunction "K_K") (pintype "passive"))
    )
    (net (code "58") (name "Net-(IC7-CSLEW)") (class "Default")
      (node (ref "C32") (pin "1") (pinfunction "1_1") (pintype "passive"))
      (node (ref "IC7") (pin "5") (pinfunction "CSLEW_5") (pintype "output"))
      (node (ref "R37") (pin "1") (pinfunction "1_1") (pintype "passive"))
      (node (ref "R39") (pin "2") (pinfunction "2_2") (pintype "passive"))
    )
    (net (code "59") (name "Net-(IC7-EN)") (class "Default")
      (node (ref "IC7") (pin "3") (pinfunction "EN_3") (pintype "input"))
      (node (ref "R36") (pin "1") (pinfunction "1_1") (pintype "passive"))
    )
    (net (code "60") (name "Net-(IC7-FAULT{slash})") (class "Default")
      (node (ref "IC7") (pin "4") (pinfunction "FAULT/_4") (pintype "output"))
      (node (ref "R38") (pin "2") (pinfunction "2_2") (pintype "passive"))
    )
    (net (code "61") (name "Net-(IC23-CSLEW)") (class "Default")
      (node (ref "C77") (pin "1") (pinfunction "1_1") (pintype "passive"))
      (node (ref "IC23") (pin "5") (pinfunction "CSLEW_5") (pintype "output"))
      (node (ref "R123") (pin "1") (pinfunction "1_1") (pintype "passive"))
      (node (ref "R124") (pin "2") (pinfunction "2_2") (pintype "passive"))
    )
    (net (code "62") (name "Net-(IC23-EN)") (class "Default")
      (node (ref "IC23") (pin "3") (pinfunction "EN_3") (pintype "input"))
      (node (ref "R121") (pin "1") (pinfunction "1_1") (pintype "passive"))
      (node (ref "R122") (pin "1") (pinfunction "1_1") (pintype "passive"))
      (node (ref "R271") (pin "1") (pinfunction "1_1") (pintype "passive"))
    )
    (net (code "63") (name "Net-(IC23-FAULT{slash})") (class "Default")
      (node (ref "IC23") (pin "4") (pinfunction "FAULT/_4") (pintype "output"))
      (node (ref "R125") (pin "1") (pinfunction "1_1") (pintype "passive"))
    )
    (net (code "64") (name "Net-(IC54-SSTX2+)") (class "Default")
      (node (ref "C252") (pin "1") (pinfunction "1_1") (pintype "passive"))
      (node (ref "IC54") (pin "13") (pinfunction "SSTX2+_13") (pintype "bidirectional"))
    )
    (net (code "65") (name "Net-(IC54-SSTX2-)") (class "Default")
      (node (ref "C249") (pin "1") (pinfunction "1_1") (pintype "passive"))
      (node (ref "IC54") (pin "14") (pinfunction "SSTX2-_14") (pintype "bidirectional"))
    )
    (net (code "66") (name "Net-(IC55-SSTX2+)") (class "Default")
      (node (ref "C253") (pin "1") (pinfunction "1_1") (pintype "passive"))
      (node (ref "IC55") (pin "13") (pinfunction "SSTX2+_13") (pintype "bidirectional"))
    )
    (net (code "67") (name "Net-(IC55-SSTX2-)") (class "Default")
      (node (ref "C250") (pin "1") (pinfunction "1_1") (pintype "passive"))
      (node (ref "IC55") (pin "14") (pinfunction "SSTX2-_14") (pintype "bidirectional"))
    )
    (net (code "68") (name "VCC3P3") (class "Default")
      (node (ref "C247") (pin "1") (pinfunction "1_1") (pintype "passive"))
      (node (ref "C248") (pin "1") (pinfunction "1_1") (pintype "passive"))
      (node (ref "C254") (pin "1") (pinfunction "1_1") (pintype "passive"))
      (node (ref "C255") (pin "1") (pinfunction "1_1") (pintype "passive"))
      (node (ref "IC52") (pin "9") (pinfunction "VCC_9") (pintype "power_in"))
      (node (ref "IC53") (pin "9") (pinfunction "VCC_9") (pintype "power_in"))
      (node (ref "IC54") (pin "17") (pinfunction "VDD_17") (pintype "power_in"))
      (node (ref "IC55") (pin "17") (pinfunction "VDD_17") (pintype "power_in"))
    )
    (net (code "69") (name "VCC5P0") (class "Default")
      (node (ref "C28") (pin "1") (pinfunction "1_1") (pintype "passive"))
      (node (ref "C32") (pin "2") (pinfunction "2_2") (pintype "passive"))
      (node (ref "C74") (pin "1") (pinfunction "1_1") (pintype "passive"))
      (node (ref "C77") (pin "2") (pinfunction "2_2") (pintype "passive"))
      (node (ref "IC23") (pin "1") (pinfunction "VIN_1") (pintype "input"))
      (node (ref "IC7") (pin "1") (pinfunction "VIN_1") (pintype "input"))
      (node (ref "R120") (pin "2") (pinfunction "2_2") (pintype "passive"))
      (node (ref "R121") (pin "2") (pinfunction "2_2") (pintype "passive"))
      (node (ref "R35") (pin "2") (pinfunction "2_2") (pintype "passive"))
      (node (ref "R36") (pin "2") (pinfunction "2_2") (pintype "passive"))
      (node (ref "R38") (pin "1") (pinfunction "1_1") (pintype "passive"))
    )
    (net (code "70") (name "VCC5P0_HDMI") (class "Default")
      (node (ref "C29") (pin "1") (pinfunction "1_1") (pintype "passive"))
      (node (ref "C30") (pin "1") (pinfunction "1_1") (pintype "passive"))
      (node (ref "C31") (pin "1") (pinfunction "1_1") (pintype "passive"))
      (node (ref "IC7") (pin "6") (pinfunction "VOUT_6") (pintype "output"))
      (node (ref "J12") (pin "18") (pinfunction "+5V_POWER_18") (pintype "power_in"))
      (node (ref "J13") (pin "18") (pinfunction "+5V_POWER_18") (pintype "power_in"))
      (node (ref "R35") (pin "1") (pinfunction "1_1") (pintype "passive"))
      (node (ref "R37") (pin "2") (pinfunction "2_2") (pintype "passive"))
    )
    (net (code "71") (name "VCC5P0_USBS") (class "Default")
      (node (ref "C251") (pin "2") (pinfunction "2_2") (pintype "passive"))
      (node (ref "C75") (pin "1") (pinfunction "1_1") (pintype "passive"))
      (node (ref "C76") (pin "2") (pinfunction "2_2") (pintype "passive"))
      (node (ref "IC23") (pin "6") (pinfunction "VOUT_6") (pintype "output"))
      (node (ref "J54") (pin "1") (pinfunction "VBUS_1") (pintype "power_in"))
      (node (ref "J54") (pin "10") (pinfunction "VBUS_10") (pintype "power_in"))
      (node (ref "R120") (pin "1") (pinfunction "1_1") (pintype "passive"))
      (node (ref "R123") (pin "2") (pinfunction "2_2") (pintype "passive"))
    )
    (net (code "72") (name "unconnected-(IC54-SSRX1+-Pad10)") (class "Default")
      (node (ref "IC54") (pin "10") (pinfunction "SSRX1+_10") (pintype "bidirectional+no_connect"))
    )
    (net (code "73") (name "unconnected-(IC54-SSRX1--Pad11)") (class "Default")
      (node (ref "IC54") (pin "11") (pinfunction "SSRX1-_11") (pintype "bidirectional+no_connect"))
    )
    (net (code "74") (name "unconnected-(IC54-SSTX1+-Pad15)") (class "Default")
      (node (ref "IC54") (pin "15") (pinfunction "SSTX1+_15") (pintype "bidirectional+no_connect"))
    )
    (net (code "75") (name "unconnected-(IC54-SSTX1--Pad16)") (class "Default")
      (node (ref "IC54") (pin "16") (pinfunction "SSTX1-_16") (pintype "bidirectional+no_connect"))
    )
    (net (code "76") (name "unconnected-(IC55-SSRX1+-Pad10)") (class "Default")
      (node (ref "IC55") (pin "10") (pinfunction "SSRX1+_10") (pintype "bidirectional+no_connect"))
    )
    (net (code "77") (name "unconnected-(IC55-SSRX1--Pad11)") (class "Default")
      (node (ref "IC55") (pin "11") (pinfunction "SSRX1-_11") (pintype "bidirectional+no_connect"))
    )
    (net (code "78") (name "unconnected-(IC55-SSTX1+-Pad15)") (class "Default")
      (node (ref "IC55") (pin "15") (pinfunction "SSTX1+_15") (pintype "bidirectional+no_connect"))
    )
    (net (code "79") (name "unconnected-(IC55-SSTX1--Pad16)") (class "Default")
      (node (ref "IC55") (pin "16") (pinfunction "SSTX1-_16") (pintype "bidirectional+no_connect"))
    )
  )
)
